# Inertial_Sensors.net
KiCad netlist of a schematic drawn in Altium Designer
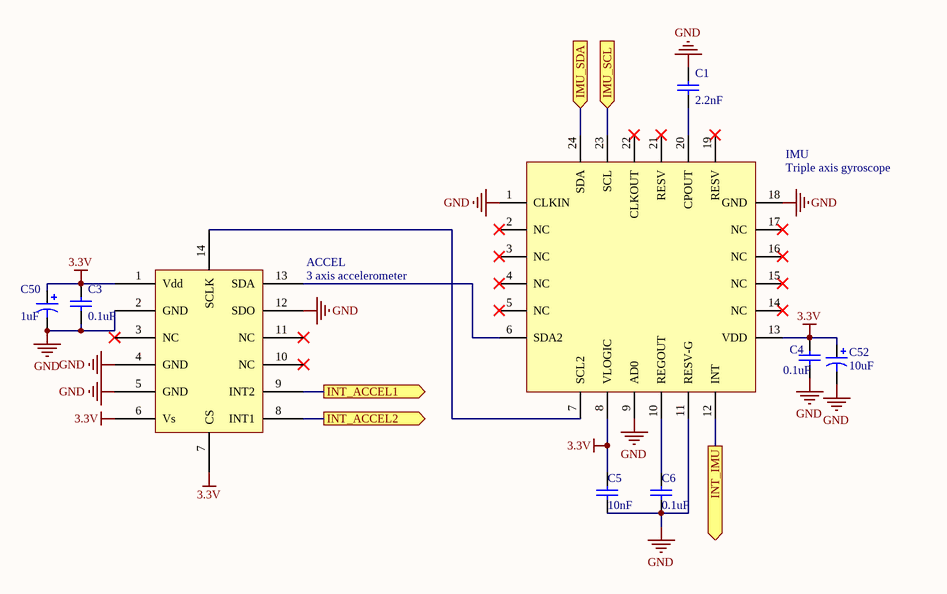
[diagram p0: Inertial Sensors.SchDoc]

(export (version "E")
  (design (tool "Eeschema 10.0.6"))
  (components
    (comp (ref "ACCEL")
      (value "3 axis accelerometer")
      (footprint "16 pin 3mmx3mm LGA")
      (description "ADXL345BCCZ-RLCT-ND")
      (fields
        (field (name "MANUFACTURER") "Analog Devices Inc")
        (field (name "MANUFACTURER PART NUMBER") "ADXL345BCCZ-RL")
      )
      (libsource (lib "Components") (part "ADXL345"))
    )
    (comp (ref "C1")
      (value "2.2nF")
      (footprint "0603_CAP")
      (description "Capacitor")
      (fields (field (name "Comment") "X7R Cap") (field (name "PUBLISHER") "Altium Limited"))
      (libsource (lib "Miscellaneous Devices") (part "Cap"))
    )
    (comp (ref "C3")
      (value "0.1uF")
      (footprint "0603_CAP")
      (description "Capacitor")
      (fields (field (name "Comment") "X7R Cap") (field (name "PUBLISHER") "Altium Limited"))
      (libsource (lib "Miscellaneous Devices") (part "Cap"))
    )
    (comp (ref "C4")
      (value "0.1uF")
      (footprint "0603_CAP")
      (description "Capacitor")
      (fields (field (name "Comment") "X7R Cap") (field (name "PUBLISHER") "Altium Limited"))
      (libsource (lib "Miscellaneous Devices") (part "Cap"))
    )
    (comp (ref "C5")
      (value "10nF")
      (footprint "0603_CAP")
      (description "Capacitor")
      (fields (field (name "Comment") "X7R Cap") (field (name "PUBLISHER") "Altium Limited"))
      (libsource (lib "Miscellaneous Devices") (part "Cap"))
    )
    (comp (ref "C6")
      (value "0.1uF")
      (footprint "0603_CAP")
      (description "Capacitor")
      (fields (field (name "Comment") "X7R Cap") (field (name "PUBLISHER") "Altium Limited"))
      (libsource (lib "Miscellaneous Devices") (part "Cap"))
    )
    (comp (ref "C50")
      (value "1uF")
      (footprint "0603_Cap")
      (description "Polarized Capacitor (Surface Mount)")
      (fields (field (name "Comment") "Cap Pol3") (field (name "PUBLISHER") "Altium Limited"))
      (libsource (lib "Miscellaneous Devices") (part "Cap Pol3"))
    )
    (comp (ref "C52")
      (value "10uF")
      (footprint "0603_Cap")
      (description "Polarized Capacitor (Surface Mount)")
      (fields (field (name "Comment") "Cap Pol3") (field (name "PUBLISHER") "Altium Limited"))
      (libsource (lib "Miscellaneous Devices") (part "Cap Pol3"))
    )
    (comp (ref "IMU")
      (value "Triple axis gyroscope")
      (footprint "QFN50P400X400X95-24N")
      (libsource (lib "Components") (part "IMU-3000"))
    )
  )
  (nets
    (net (code "1") (name "/IMU_SCL") (class "Default")
      (node (ref "IMU") (pin "23") (pinfunction "SCL_23") (pintype "passive"))
    )
    (net (code "2") (name "/IMU_SDA") (class "Default")
      (node (ref "IMU") (pin "24") (pinfunction "SDA_24") (pintype "passive"))
    )
    (net (code "3") (name "/INT_ACCEL1") (class "Default")
      (node (ref "ACCEL") (pin "9") (pinfunction "INT2_9") (pintype "passive"))
    )
    (net (code "4") (name "/INT_ACCEL2") (class "Default")
      (node (ref "ACCEL") (pin "8") (pinfunction "INT1_8") (pintype "passive"))
    )
    (net (code "5") (name "/INT_IMU") (class "Default")
      (node (ref "IMU") (pin "12") (pinfunction "INT_12") (pintype "passive"))
    )
    (net (code "6") (name "3.3V") (class "Default")
      (node (ref "ACCEL") (pin "1") (pinfunction "Vdd_1") (pintype "power_in"))
      (node (ref "ACCEL") (pin "6") (pinfunction "Vs_6") (pintype "passive"))
      (node (ref "ACCEL") (pin "7") (pinfunction "CS_7") (pintype "passive"))
      (node (ref "C3") (pin "2") (pinfunction "2_2") (pintype "passive"))
      (node (ref "C4") (pin "2") (pinfunction "2_2") (pintype "passive"))
      (node (ref "C5") (pin "1") (pinfunction "1_1") (pintype "passive"))
      (node (ref "C50") (pin "1") (pinfunction "1_1") (pintype "passive"))
      (node (ref "C52") (pin "1") (pinfunction "1_1") (pintype "passive"))
      (node (ref "IMU") (pin "13") (pinfunction "VDD_13") (pintype "passive"))
      (node (ref "IMU") (pin "8") (pinfunction "VLOGIC_8") (pintype "passive"))
    )
    (net (code "7") (name "GND") (class "Default")
      (node (ref "ACCEL") (pin "12") (pinfunction "SDO_12") (pintype "passive"))
      (node (ref "ACCEL") (pin "2") (pinfunction "GND_2") (pintype "passive"))
      (node (ref "ACCEL") (pin "4") (pinfunction "GND_4") (pintype "passive"))
      (node (ref "ACCEL") (pin "5") (pinfunction "GND_5") (pintype "passive"))
      (node (ref "C1") (pin "1") (pinfunction "1_1") (pintype "passive"))
      (node (ref "C3") (pin "1") (pinfunction "1_1") (pintype "passive"))
      (node (ref "C4") (pin "1") (pinfunction "1_1") (pintype "passive"))
      (node (ref "C5") (pin "2") (pinfunction "2_2") (pintype "passive"))
      (node (ref "C50") (pin "2") (pinfunction "2_2") (pintype "passive"))
      (node (ref "C52") (pin "2") (pinfunction "2_2") (pintype "passive"))
      (node (ref "C6") (pin "1") (pinfunction "1_1") (pintype "passive"))
      (node (ref "IMU") (pin "1") (pinfunction "CLKIN_1") (pintype "passive"))
      (node (ref "IMU") (pin "11") (pinfunction "RESV-G_11") (pintype "passive"))
      (node (ref "IMU") (pin "18") (pinfunction "GND_18") (pintype "passive"))
      (node (ref "IMU") (pin "9") (pinfunction "AD0_9") (pintype "passive"))
    )
    (net (code "8") (name "Net-(ACCEL-SCLK)") (class "Default")
      (node (ref "ACCEL") (pin "14") (pinfunction "SCLK_14") (pintype "power_in"))
      (node (ref "IMU") (pin "7") (pinfunction "SCL2_7") (pintype "passive"))
    )
    (net (code "9") (name "Net-(ACCEL-SDA)") (class "Default")
      (node (ref "ACCEL") (pin "13") (pinfunction "SDA_13") (pintype "passive"))
      (node (ref "IMU") (pin "6") (pinfunction "SDA2_6") (pintype "passive"))
    )
    (net (code "10") (name "Net-(IMU-CPOUT)") (class "Default")
      (node (ref "C1") (pin "2") (pinfunction "2_2") (pintype "passive"))
      (node (ref "IMU") (pin "20") (pinfunction "CPOUT_20") (pintype "passive"))
    )
    (net (code "11") (name "Net-(IMU-REGOUT)") (class "Default")
      (node (ref "C6") (pin "2") (pinfunction "2_2") (pintype "passive"))
      (node (ref "IMU") (pin "10") (pinfunction "REGOUT_10") (pintype "passive"))
    )
    (net (code "12") (name "unconnected-(ACCEL-NC-Pad3)") (class "Default")
      (node (ref "ACCEL") (pin "3") (pinfunction "NC_3") (pintype "passive+no_connect"))
    )
    (net (code "13") (name "unconnected-(ACCEL-NC-Pad10)") (class "Default")
      (node (ref "ACCEL") (pin "10") (pinfunction "NC_10") (pintype "passive+no_connect"))
    )
    (net (code "14") (name "unconnected-(ACCEL-NC-Pad11)") (class "Default")
      (node (ref "ACCEL") (pin "11") (pinfunction "NC_11") (pintype "passive+no_connect"))
    )
    (net (code "15") (name "unconnected-(IMU-CLKOUT-Pad22)") (class "Default")
      (node (ref "IMU") (pin "22") (pinfunction "CLKOUT_22") (pintype "passive+no_connect"))
    )
    (net (code "16") (name "unconnected-(IMU-NC-Pad2)") (class "Default")
      (node (ref "IMU") (pin "2") (pinfunction "NC_2") (pintype "passive+no_connect"))
    )
    (net (code "17") (name "unconnected-(IMU-NC-Pad3)") (class "Default")
      (node (ref "IMU") (pin "3") (pinfunction "NC_3") (pintype "passive+no_connect"))
    )
    (net (code "18") (name "unconnected-(IMU-NC-Pad4)") (class "Default")
      (node (ref "IMU") (pin "4") (pinfunction "NC_4") (pintype "passive+no_connect"))
    )
    (net (code "19") (name "unconnected-(IMU-NC-Pad5)") (class "Default")
      (node (ref "IMU") (pin "5") (pinfunction "NC_5") (pintype "passive+no_connect"))
    )
    (net (code "20") (name "unconnected-(IMU-NC-Pad14)") (class "Default")
      (node (ref "IMU") (pin "14") (pinfunction "NC_14") (pintype "passive+no_connect"))
    )
    (net (code "21") (name "unconnected-(IMU-NC-Pad15)") (class "Default")
      (node (ref "IMU") (pin "15") (pinfunction "NC_15") (pintype "passive+no_connect"))
    )
    (net (code "22") (name "unconnected-(IMU-NC-Pad16)") (class "Default")
      (node (ref "IMU") (pin "16") (pinfunction "NC_16") (pintype "passive+no_connect"))
    )
    (net (code "23") (name "unconnected-(IMU-NC-Pad17)") (class "Default")
      (node (ref "IMU") (pin "17") (pinfunction "NC_17") (pintype "passive+no_connect"))
    )
    (net (code "24") (name "unconnected-(IMU-RESV-Pad19)") (class "Default")
      (node (ref "IMU") (pin "19") (pinfunction "RESV_19") (pintype "passive+no_connect"))
    )
    (net (code "25") (name "unconnected-(IMU-RESV-Pad21)") (class "Default")
      (node (ref "IMU") (pin "21") (pinfunction "RESV_21") (pintype "passive+no_connect"))
    )
  )
)
